# Schematic.net
KiCad netlist of a schematic drawn in EAGLE
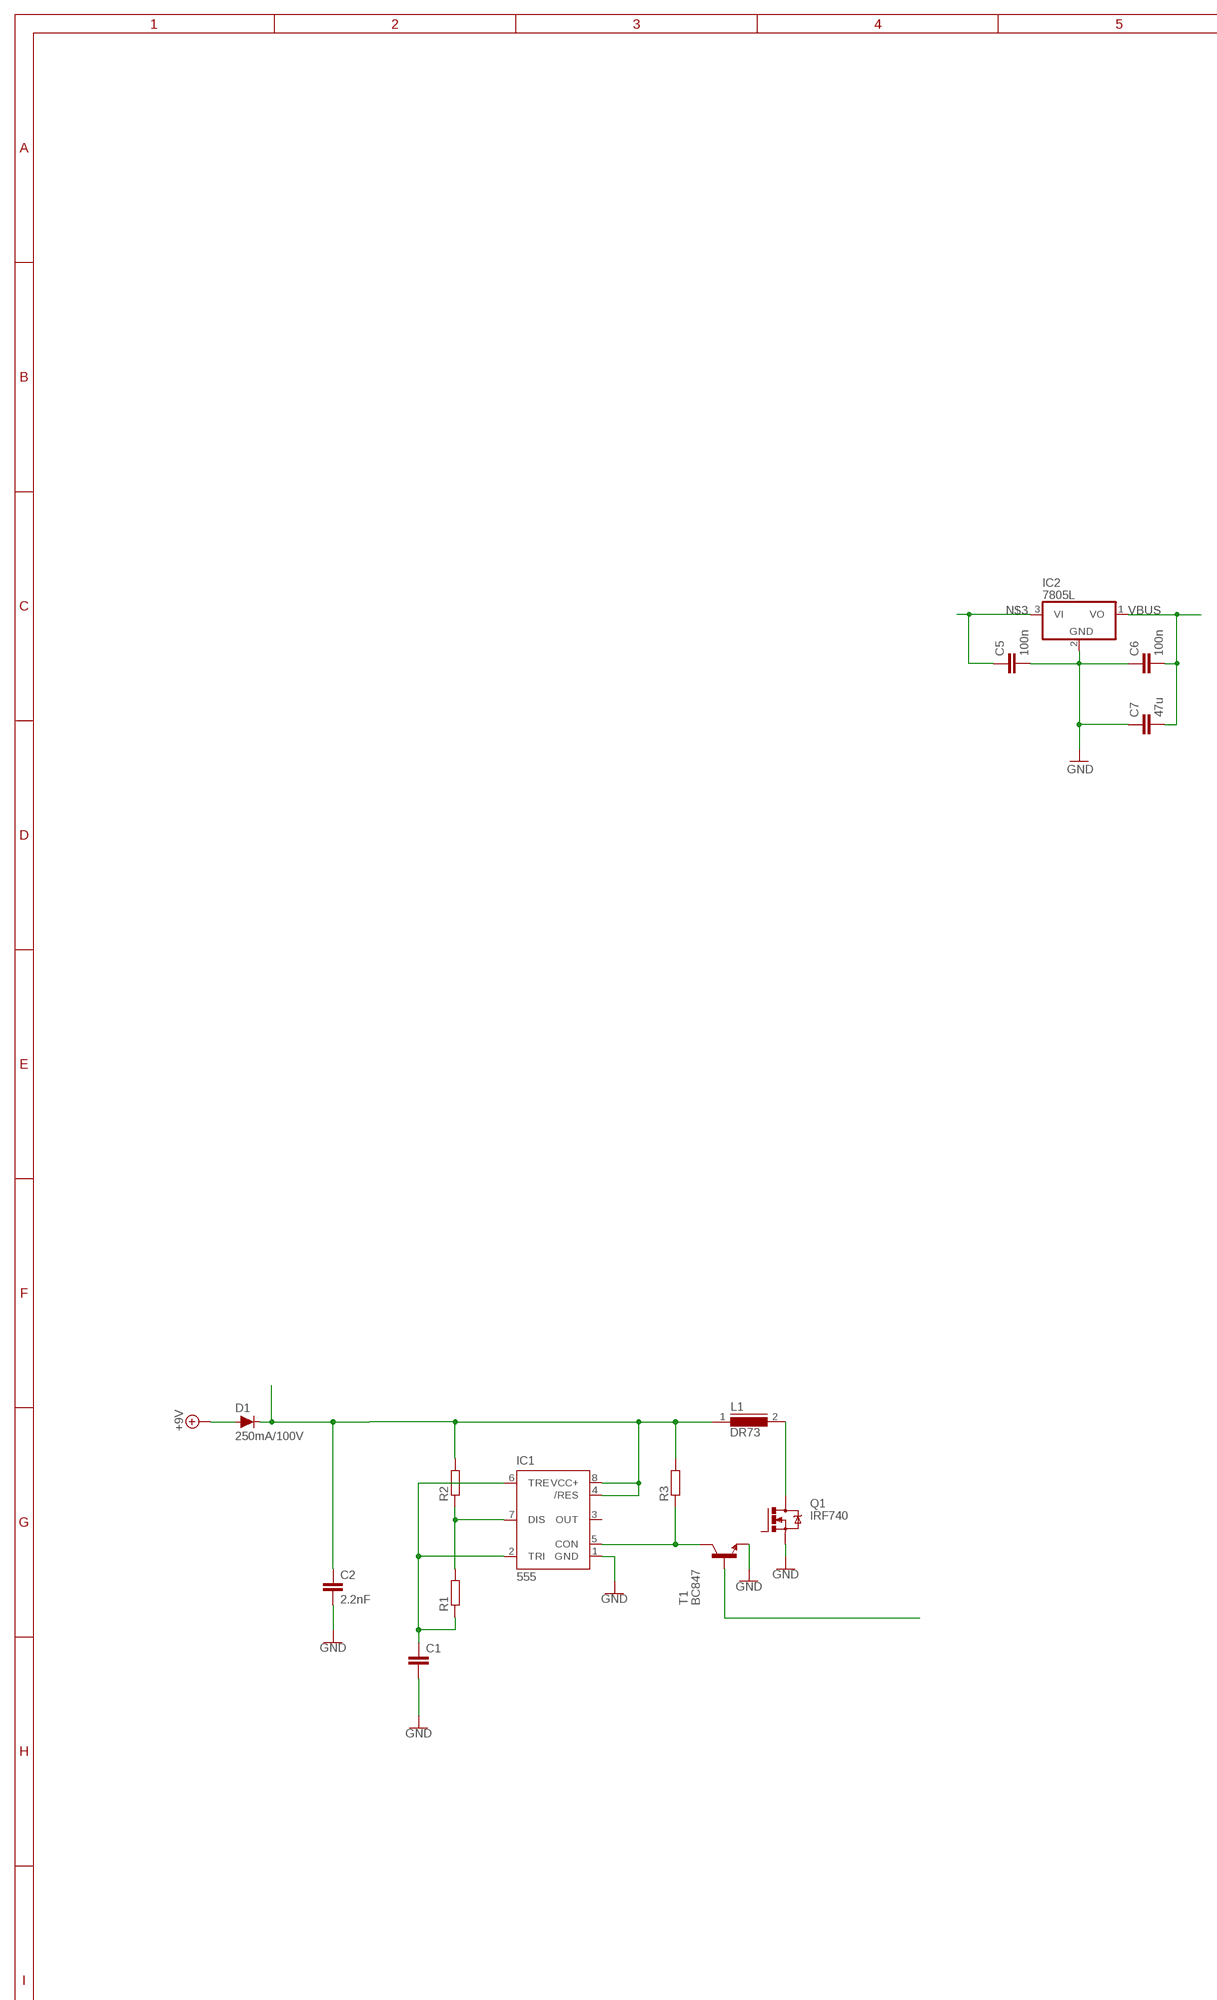
[diagram p0: schematic, sheet 1, part 1 of 2]
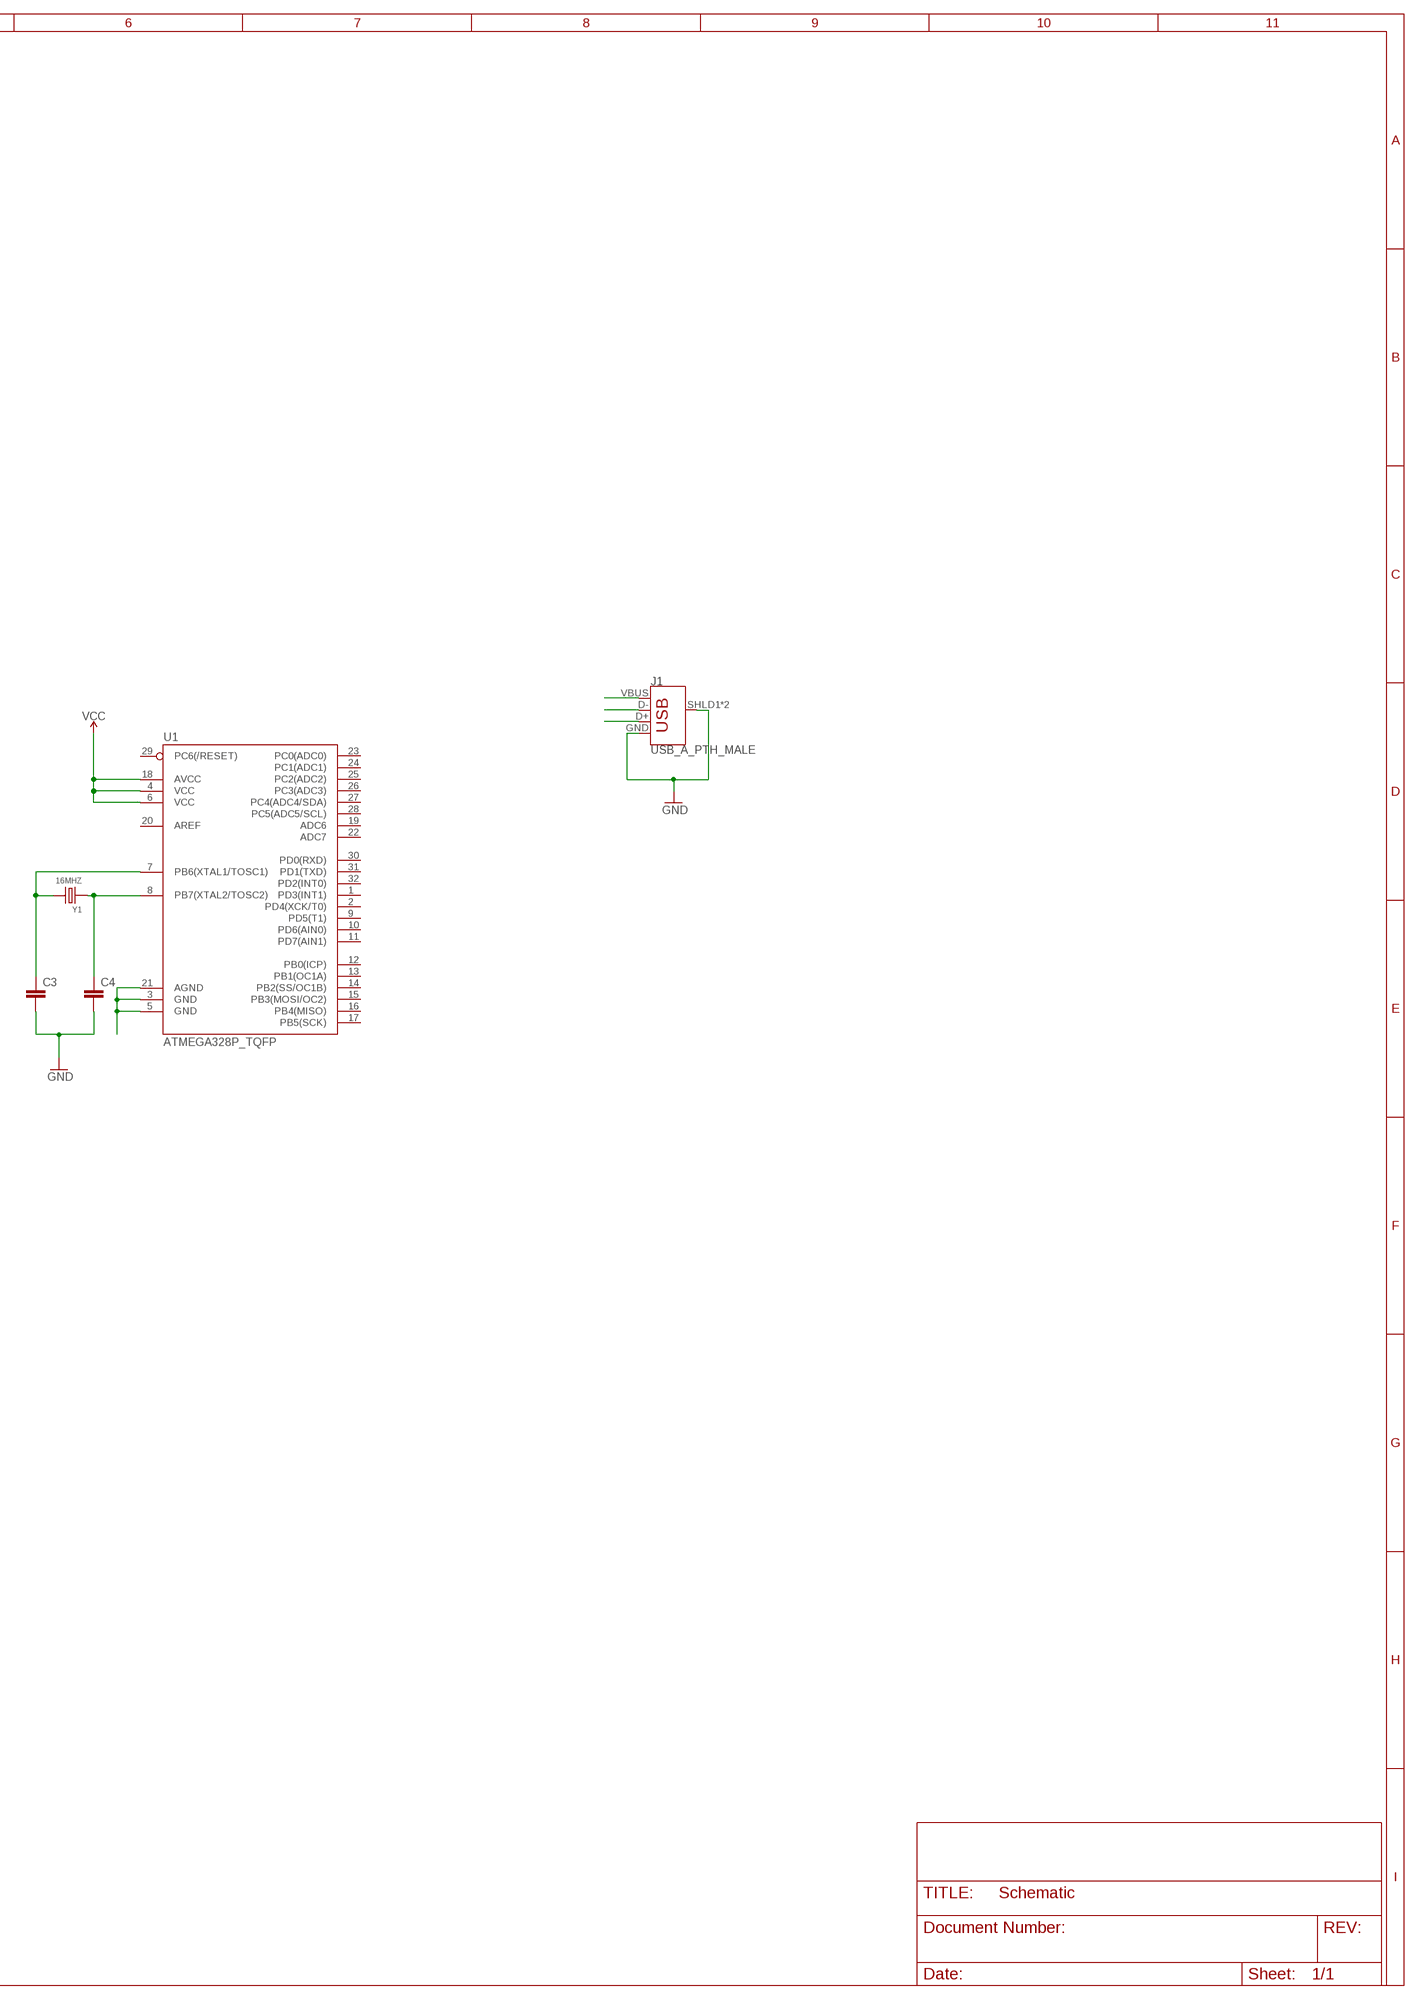
[diagram p1: schematic, sheet 1, part 2 of 2]

(export (version "E")
  (design (tool "Eeschema 10.0.6"))
  (components
    (comp (ref "C1")
      (value "C-EUC0805")
      (footprint "eagle-import:C0805")
      (libsource (lib "eagle-import") (part "C-EUC0805"))
    )
    (comp (ref "C2")
      (value "2.2nF")
      (footprint "eagle-import:0603")
      (libsource (lib "eagle-import") (part "2.2NF/2200PF-0603-50V-10%"))
    )
    (comp (ref "C3")
      (value "C-EUC0805")
      (footprint "eagle-import:C0805")
      (libsource (lib "eagle-import") (part "C-EUC0805"))
    )
    (comp (ref "C4")
      (value "C-EUC0805")
      (footprint "eagle-import:C0805")
      (libsource (lib "eagle-import") (part "C-EUC0805"))
    )
    (comp (ref "C5")
      (value "100n")
      (footprint "eagle-import:C0805")
      (libsource (lib "eagle-import") (part "C-EUC0805"))
    )
    (comp (ref "C6")
      (value "100n")
      (footprint "eagle-import:C0805")
      (libsource (lib "eagle-import") (part "C-EUC0805"))
    )
    (comp (ref "C7")
      (value "47u")
      (footprint "eagle-import:C0805")
      (libsource (lib "eagle-import") (part "C-EUC0805"))
    )
    (comp (ref "D1")
      (value "250mA/100V")
      (footprint "eagle-import:SOD-323")
      (libsource (lib "eagle-import") (part "DIODE-BAS16J"))
    )
    (comp (ref "IC1")
      (value "555")
      (footprint "eagle-import:SO08")
      (libsource (lib "eagle-import") (part "555D"))
    )
    (comp (ref "IC2")
      (value "7805L")
      (footprint "eagle-import:TO92")
      (libsource (lib "eagle-import") (part "78L05"))
    )
    (comp (ref "J1")
      (value "USB_A_PTH_MALE")
      (footprint "eagle-import:USB-A-H")
      (libsource (lib "eagle-import") (part "USB_A_PTH_MALE"))
    )
    (comp (ref "L1")
      (value "DR73")
      (footprint "eagle-import:DR73")
      (libsource (lib "eagle-import") (part "DR73"))
    )
    (comp (ref "Q1")
      (value "IRF740")
      (footprint "eagle-import:TO220BV")
      (libsource (lib "eagle-import") (part "IRF740"))
    )
    (comp (ref "R1")
      (value "R-EU_R0805")
      (footprint "eagle-import:R0805")
      (libsource (lib "eagle-import") (part "R-EU_R0805"))
    )
    (comp (ref "R2")
      (value "R-EU_R0805")
      (footprint "eagle-import:R0805")
      (libsource (lib "eagle-import") (part "R-EU_R0805"))
    )
    (comp (ref "R3")
      (value "R-EU_M0805")
      (footprint "eagle-import:M0805")
      (libsource (lib "eagle-import") (part "R-EU_M0805"))
    )
    (comp (ref "T1")
      (value "BC847")
      (footprint "eagle-import:SOT23")
      (libsource (lib "eagle-import") (part "BC847"))
    )
    (comp (ref "U1")
      (value "ATMEGA328P_TQFP")
      (footprint "eagle-import:TQFP32-08")
      (libsource (lib "eagle-import") (part "ATMEGA328P_TQFP"))
    )
    (comp (ref "Y1")
      (value "16MHZ")
      (footprint "eagle-import:HC49US")
      (fields (field (name "MPN") "49S/18PF"))
      (libsource (lib "eagle-import") (part "DIP-CRYSTAL-16MHZ-18PF-30PPM-50R(HC49US)"))
    )
  )
  (nets
    (net (code "1") (name "+9V") (class "Default")
      (node (ref "D1") (pin "A") (pinfunction "A_A") (pintype "passive"))
    )
    (net (code "2") (name "/N$3") (class "Default")
      (node (ref "C2") (pin "1") (pinfunction "1_1") (pintype "passive"))
      (node (ref "C5") (pin "1") (pinfunction "1_1") (pintype "passive"))
      (node (ref "D1") (pin "C") (pinfunction "C_C") (pintype "passive"))
      (node (ref "IC1") (pin "4") (pinfunction "/RES_4") (pintype "input"))
      (node (ref "IC1") (pin "8") (pinfunction "VCC+_8") (pintype "power_in"))
      (node (ref "IC2") (pin "3") (pinfunction "VI_3") (pintype "input"))
      (node (ref "L1") (pin "1") (pinfunction "1_1") (pintype "passive"))
      (node (ref "R2") (pin "2") (pinfunction "2_2") (pintype "passive"))
      (node (ref "R3") (pin "2") (pinfunction "2_2") (pintype "passive"))
    )
    (net (code "3") (name "/VBUS") (class "Default")
      (node (ref "C6") (pin "2") (pinfunction "2_2") (pintype "passive"))
      (node (ref "C7") (pin "2") (pinfunction "2_2") (pintype "passive"))
      (node (ref "IC2") (pin "1") (pinfunction "VO_1") (pintype "passive"))
      (node (ref "J1") (pin "VBUS") (pinfunction "VBUS_VBUS") (pintype "power_in"))
    )
    (net (code "4") (name "GND") (class "Default")
      (node (ref "C1") (pin "2") (pinfunction "2_2") (pintype "passive"))
      (node (ref "C2") (pin "2") (pinfunction "2_2") (pintype "passive"))
      (node (ref "C3") (pin "2") (pinfunction "2_2") (pintype "passive"))
      (node (ref "C4") (pin "2") (pinfunction "2_2") (pintype "passive"))
      (node (ref "C5") (pin "2") (pinfunction "2_2") (pintype "passive"))
      (node (ref "C6") (pin "1") (pinfunction "1_1") (pintype "passive"))
      (node (ref "C7") (pin "1") (pinfunction "1_1") (pintype "passive"))
      (node (ref "IC1") (pin "1") (pinfunction "GND_1") (pintype "power_in"))
      (node (ref "IC2") (pin "2") (pinfunction "GND_2") (pintype "passive"))
      (node (ref "J1") (pin "GND") (pinfunction "GND_GND") (pintype "power_in"))
      (node (ref "J1") (pin "SHLD1") (pinfunction "SHIELD_SHLD1") (pintype "bidirectional"))
      (node (ref "J1") (pin "SHLD2") (pinfunction "SHIELD_SHLD2") (pintype "bidirectional"))
      (node (ref "Q1") (pin "S") (pinfunction "S_S") (pintype "passive"))
      (node (ref "T1") (pin "2") (pinfunction "E_2") (pintype "passive"))
    )
    (net (code "5") (name "Net-(IC1-CON)") (class "Default")
      (node (ref "IC1") (pin "5") (pinfunction "CON_5") (pintype "input"))
      (node (ref "R3") (pin "1") (pinfunction "1_1") (pintype "passive"))
      (node (ref "T1") (pin "3") (pinfunction "C_3") (pintype "passive"))
    )
    (net (code "6") (name "Net-(IC1-DIS)") (class "Default")
      (node (ref "IC1") (pin "7") (pinfunction "DIS_7") (pintype "input"))
      (node (ref "R1") (pin "2") (pinfunction "2_2") (pintype "passive"))
      (node (ref "R2") (pin "1") (pinfunction "1_1") (pintype "passive"))
    )
    (net (code "7") (name "Net-(IC1-TRE)") (class "Default")
      (node (ref "C1") (pin "1") (pinfunction "1_1") (pintype "passive"))
      (node (ref "IC1") (pin "2") (pinfunction "TRI_2") (pintype "input"))
      (node (ref "IC1") (pin "6") (pinfunction "TRE_6") (pintype "input"))
      (node (ref "R1") (pin "1") (pinfunction "1_1") (pintype "passive"))
    )
    (net (code "8") (name "Net-(L1-Pad2)") (class "Default")
      (node (ref "L1") (pin "2") (pinfunction "2_2") (pintype "passive"))
      (node (ref "Q1") (pin "D") (pinfunction "D_D") (pintype "passive"))
    )
    (net (code "9") (name "Net-(U1-AGND)") (class "Default")
      (node (ref "U1") (pin "21") (pinfunction "AGND_21") (pintype "bidirectional"))
      (node (ref "U1") (pin "3") (pinfunction "GND_3") (pintype "bidirectional"))
      (node (ref "U1") (pin "5") (pinfunction "GND_5") (pintype "bidirectional"))
    )
    (net (code "10") (name "Net-(U1-PB6(XTAL1{slash}TOSC1))") (class "Default")
      (node (ref "C3") (pin "1") (pinfunction "1_1") (pintype "passive"))
      (node (ref "U1") (pin "7") (pinfunction "PB6(XTAL1/TOSC1)_7") (pintype "bidirectional"))
      (node (ref "Y1") (pin "2") (pinfunction "2_2") (pintype "passive"))
    )
    (net (code "11") (name "Net-(U1-PB7(XTAL2{slash}TOSC2))") (class "Default")
      (node (ref "C4") (pin "1") (pinfunction "1_1") (pintype "passive"))
      (node (ref "U1") (pin "8") (pinfunction "PB7(XTAL2/TOSC2)_8") (pintype "bidirectional"))
      (node (ref "Y1") (pin "1") (pinfunction "1_1") (pintype "passive"))
    )
    (net (code "12") (name "VCC") (class "Default")
      (node (ref "U1") (pin "18") (pinfunction "AVCC_18") (pintype "bidirectional"))
      (node (ref "U1") (pin "4") (pinfunction "VCC_4") (pintype "bidirectional"))
      (node (ref "U1") (pin "6") (pinfunction "VCC_6") (pintype "bidirectional"))
    )
    (net (code "13") (name "unconnected-(IC1-OUT-Pad3)") (class "Default")
      (node (ref "IC1") (pin "3") (pinfunction "OUT_3") (pintype "output"))
    )
    (net (code "14") (name "unconnected-(J1-PadD+)") (class "Default")
      (node (ref "J1") (pin "D+") (pinfunction "D+_D+") (pintype "bidirectional"))
    )
    (net (code "15") (name "unconnected-(J1-PadD-)") (class "Default")
      (node (ref "J1") (pin "D-") (pinfunction "D-_D-") (pintype "bidirectional"))
    )
    (net (code "16") (name "unconnected-(Q1-PadG)") (class "Default")
      (node (ref "Q1") (pin "G") (pinfunction "G_G") (pintype "passive"))
    )
    (net (code "17") (name "unconnected-(T1-B-Pad1)") (class "Default")
      (node (ref "T1") (pin "1") (pinfunction "B_1") (pintype "passive"))
    )
    (net (code "18") (name "unconnected-(U1-ADC6-Pad19)") (class "Default")
      (node (ref "U1") (pin "19") (pinfunction "ADC6_19") (pintype "bidirectional"))
    )
    (net (code "19") (name "unconnected-(U1-ADC7-Pad22)") (class "Default")
      (node (ref "U1") (pin "22") (pinfunction "ADC7_22") (pintype "bidirectional"))
    )
    (net (code "20") (name "unconnected-(U1-AREF-Pad20)") (class "Default")
      (node (ref "U1") (pin "20") (pinfunction "AREF_20") (pintype "bidirectional"))
    )
    (net (code "21") (name "unconnected-(U1-PB0(ICP)-Pad12)") (class "Default")
      (node (ref "U1") (pin "12") (pinfunction "PB0(ICP)_12") (pintype "bidirectional"))
    )
    (net (code "22") (name "unconnected-(U1-PB1(OC1A)-Pad13)") (class "Default")
      (node (ref "U1") (pin "13") (pinfunction "PB1(OC1A)_13") (pintype "bidirectional"))
    )
    (net (code "23") (name "unconnected-(U1-PB2(SS{slash}OC1B)-Pad14)") (class "Default")
      (node (ref "U1") (pin "14") (pinfunction "PB2(SS/OC1B)_14") (pintype "bidirectional"))
    )
    (net (code "24") (name "unconnected-(U1-PB3(MOSI{slash}OC2)-Pad15)") (class "Default")
      (node (ref "U1") (pin "15") (pinfunction "PB3(MOSI/OC2)_15") (pintype "bidirectional"))
    )
    (net (code "25") (name "unconnected-(U1-PB4(MISO)-Pad16)") (class "Default")
      (node (ref "U1") (pin "16") (pinfunction "PB4(MISO)_16") (pintype "bidirectional"))
    )
    (net (code "26") (name "unconnected-(U1-PB5(SCK)-Pad17)") (class "Default")
      (node (ref "U1") (pin "17") (pinfunction "PB5(SCK)_17") (pintype "bidirectional"))
    )
    (net (code "27") (name "unconnected-(U1-PC0(ADC0)-Pad23)") (class "Default")
      (node (ref "U1") (pin "23") (pinfunction "PC0(ADC0)_23") (pintype "bidirectional"))
    )
    (net (code "28") (name "unconnected-(U1-PC1(ADC1)-Pad24)") (class "Default")
      (node (ref "U1") (pin "24") (pinfunction "PC1(ADC1)_24") (pintype "bidirectional"))
    )
    (net (code "29") (name "unconnected-(U1-PC2(ADC2)-Pad25)") (class "Default")
      (node (ref "U1") (pin "25") (pinfunction "PC2(ADC2)_25") (pintype "bidirectional"))
    )
    (net (code "30") (name "unconnected-(U1-PC3(ADC3)-Pad26)") (class "Default")
      (node (ref "U1") (pin "26") (pinfunction "PC3(ADC3)_26") (pintype "bidirectional"))
    )
    (net (code "31") (name "unconnected-(U1-PC4(ADC4{slash}SDA)-Pad27)") (class "Default")
      (node (ref "U1") (pin "27") (pinfunction "PC4(ADC4/SDA)_27") (pintype "bidirectional"))
    )
    (net (code "32") (name "unconnected-(U1-PC5(ADC5{slash}SCL)-Pad28)") (class "Default")
      (node (ref "U1") (pin "28") (pinfunction "PC5(ADC5/SCL)_28") (pintype "bidirectional"))
    )
    (net (code "33") (name "unconnected-(U1-PC6({slash}RESET)-Pad29)") (class "Default")
      (node (ref "U1") (pin "29") (pinfunction "PC6(/RESET)_29") (pintype "bidirectional"))
    )
    (net (code "34") (name "unconnected-(U1-PD0(RXD)-Pad30)") (class "Default")
      (node (ref "U1") (pin "30") (pinfunction "PD0(RXD)_30") (pintype "bidirectional"))
    )
    (net (code "35") (name "unconnected-(U1-PD1(TXD)-Pad31)") (class "Default")
      (node (ref "U1") (pin "31") (pinfunction "PD1(TXD)_31") (pintype "bidirectional"))
    )
    (net (code "36") (name "unconnected-(U1-PD2(INT0)-Pad32)") (class "Default")
      (node (ref "U1") (pin "32") (pinfunction "PD2(INT0)_32") (pintype "bidirectional"))
    )
    (net (code "37") (name "unconnected-(U1-PD3(INT1)-Pad1)") (class "Default")
      (node (ref "U1") (pin "1") (pinfunction "PD3(INT1)_1") (pintype "bidirectional"))
    )
    (net (code "38") (name "unconnected-(U1-PD4(XCK{slash}T0)-Pad2)") (class "Default")
      (node (ref "U1") (pin "2") (pinfunction "PD4(XCK/T0)_2") (pintype "bidirectional"))
    )
    (net (code "39") (name "unconnected-(U1-PD5(T1)-Pad9)") (class "Default")
      (node (ref "U1") (pin "9") (pinfunction "PD5(T1)_9") (pintype "bidirectional"))
    )
    (net (code "40") (name "unconnected-(U1-PD6(AIN0)-Pad10)") (class "Default")
      (node (ref "U1") (pin "10") (pinfunction "PD6(AIN0)_10") (pintype "bidirectional"))
    )
    (net (code "41") (name "unconnected-(U1-PD7(AIN1)-Pad11)") (class "Default")
      (node (ref "U1") (pin "11") (pinfunction "PD7(AIN1)_11") (pintype "bidirectional"))
    )
  )
)
